# LED_RGB.net
KiCad netlist of a schematic drawn in Altium Designer
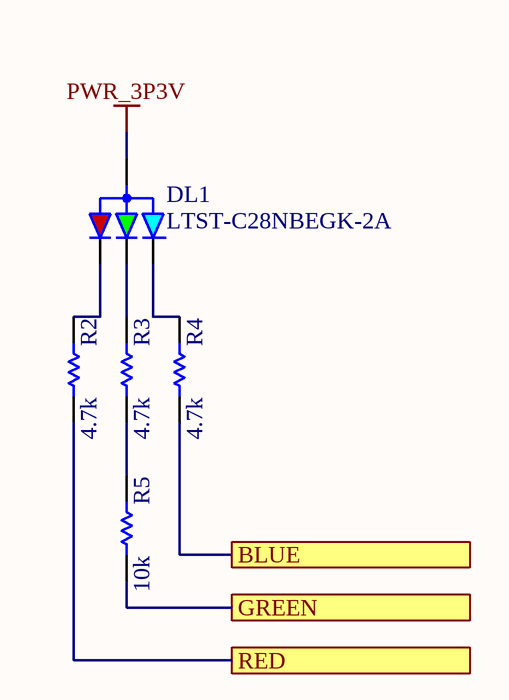
[diagram p0: LED_RGB.SchDoc]

(export (version "E")
  (design (tool "Eeschema 10.0.6"))
  (components
    (comp (ref "DL1")
      (value "LTST-C28NBEGK-2A")
      (footprint "SMLP34RGB2W")
      (description "LED RGB DIFFUSED PICOLED SMD")
      (fields (field (name "MANUFACTURER") "Liteon"))
      (libsource (lib "Clean") (part "SMLP34RGB2W3"))
    )
    (comp (ref "R2")
      (value "4.7k")
      (footprint "RES-0402")
      (description "RES CHIP 0402 4k7 1% 1/16W")
      (fields (field (name "PART NUMBER") "RC0402FR-074K7L") (field (name "TOLERANCE") "1%"))
      (libsource (lib "Clean") (part "RES"))
    )
    (comp (ref "R3")
      (value "4.7k")
      (footprint "RES-0402")
      (description "RES CHIP 0402 4k7 1% 1/16W")
      (fields (field (name "PART NUMBER") "RC0402FR-074K7L") (field (name "TOLERANCE") "1%"))
      (libsource (lib "Clean") (part "RES"))
    )
    (comp (ref "R4")
      (value "4.7k")
      (footprint "RES-0402")
      (description "RES CHIP 0402 4k7 1% 1/16W")
      (fields (field (name "PART NUMBER") "RC0402FR-074K7L") (field (name "TOLERANCE") "1%"))
      (libsource (lib "Clean") (part "RES"))
    )
    (comp (ref "R5")
      (value "10k")
      (footprint "RES-0402")
      (description "RES CHIP 0402 10k 1% 1/16W")
      (fields (field (name "PART NUMBER") "CRCW040210K0FKED") (field (name "MANUFACTURER") "Vishay"))
      (libsource (lib "Clean") (part "RES"))
    )
  )
  (nets
    (net (code "1") (name "/BLUE") (class "Default")
      (node (ref "R4") (pin "1") (pinfunction "1_1") (pintype "passive"))
    )
    (net (code "2") (name "/GREEN") (class "Default")
      (node (ref "R5") (pin "2") (pinfunction "2_2") (pintype "passive"))
    )
    (net (code "3") (name "/RED") (class "Default")
      (node (ref "R2") (pin "1") (pinfunction "1_1") (pintype "passive"))
    )
    (net (code "4") (name "Net-(DL1-BLUE_C)") (class "Default")
      (node (ref "DL1") (pin "3") (pinfunction "BLUE_C_3") (pintype "passive"))
      (node (ref "R4") (pin "2") (pinfunction "2_2") (pintype "passive"))
    )
    (net (code "5") (name "Net-(DL1-GREEN_C)") (class "Default")
      (node (ref "DL1") (pin "4") (pinfunction "GREEN_C_4") (pintype "passive"))
      (node (ref "R3") (pin "2") (pinfunction "2_2") (pintype "passive"))
    )
    (net (code "6") (name "Net-(DL1-RED_C)") (class "Default")
      (node (ref "DL1") (pin "2") (pinfunction "RED_C_2") (pintype "passive"))
      (node (ref "R2") (pin "2") (pinfunction "2_2") (pintype "passive"))
    )
    (net (code "7") (name "Net-(R3-Pad1)") (class "Default")
      (node (ref "R3") (pin "1") (pinfunction "1_1") (pintype "passive"))
      (node (ref "R5") (pin "1") (pinfunction "1_1") (pintype "passive"))
    )
    (net (code "8") (name "PWR_3P3V") (class "Default")
      (node (ref "DL1") (pin "1") (pinfunction "ANODE_1") (pintype "passive"))
    )
  )
)
